# tweeq-Proto_Motor.net
KiCad netlist of a schematic drawn in EAGLE
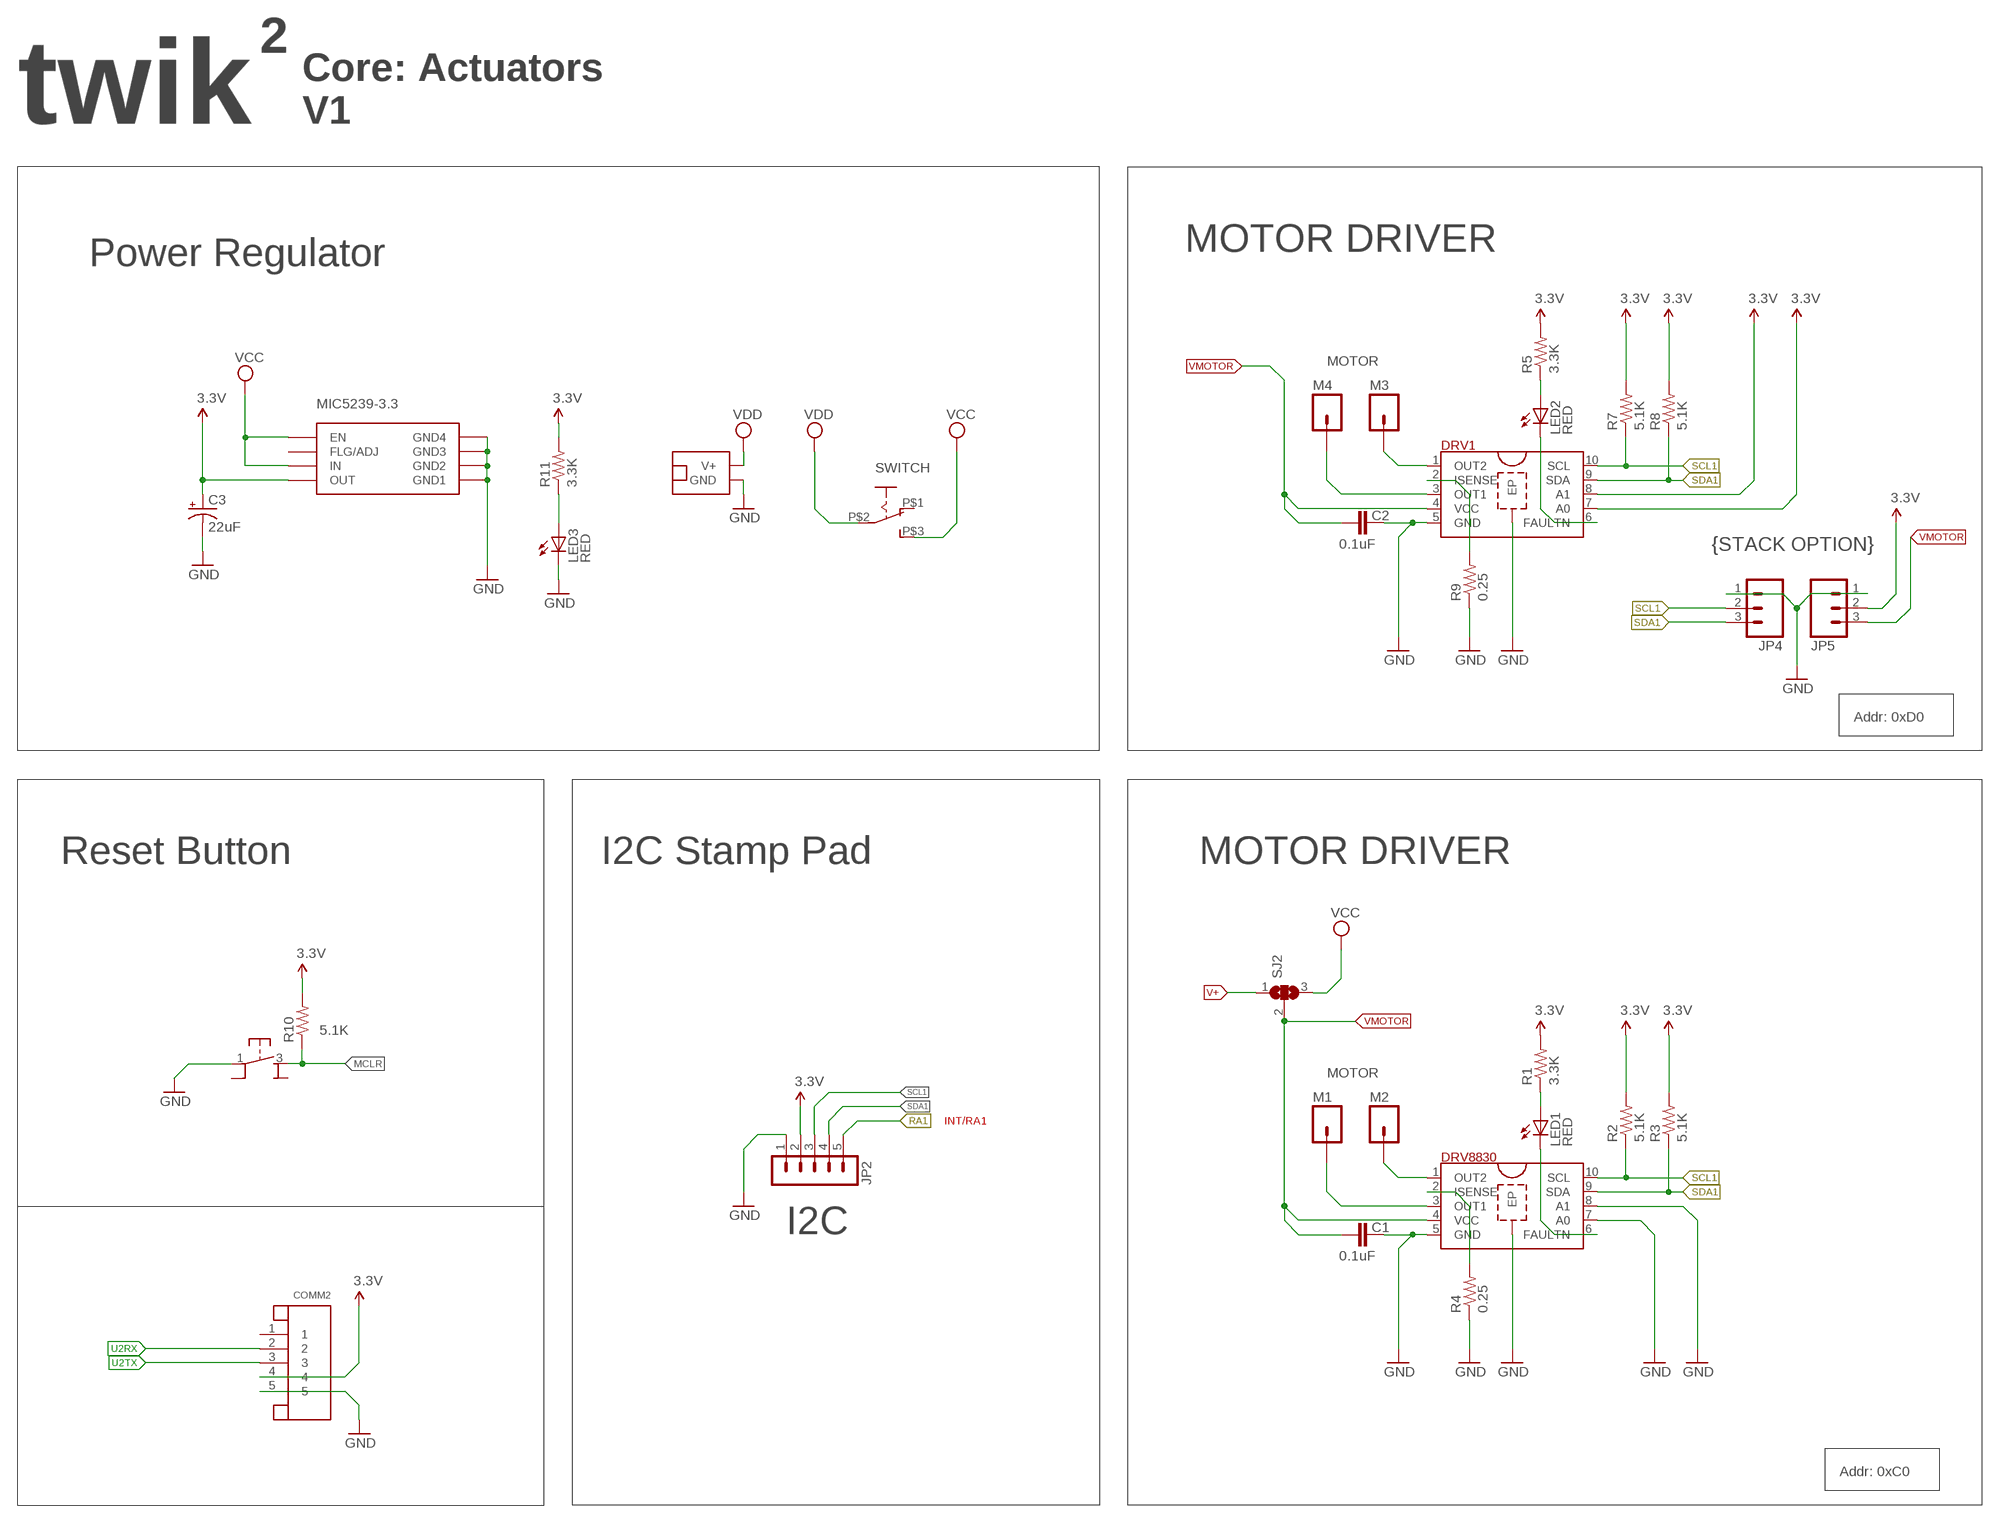
[diagram p0: schematic, sheet 1, part 1 of 2]
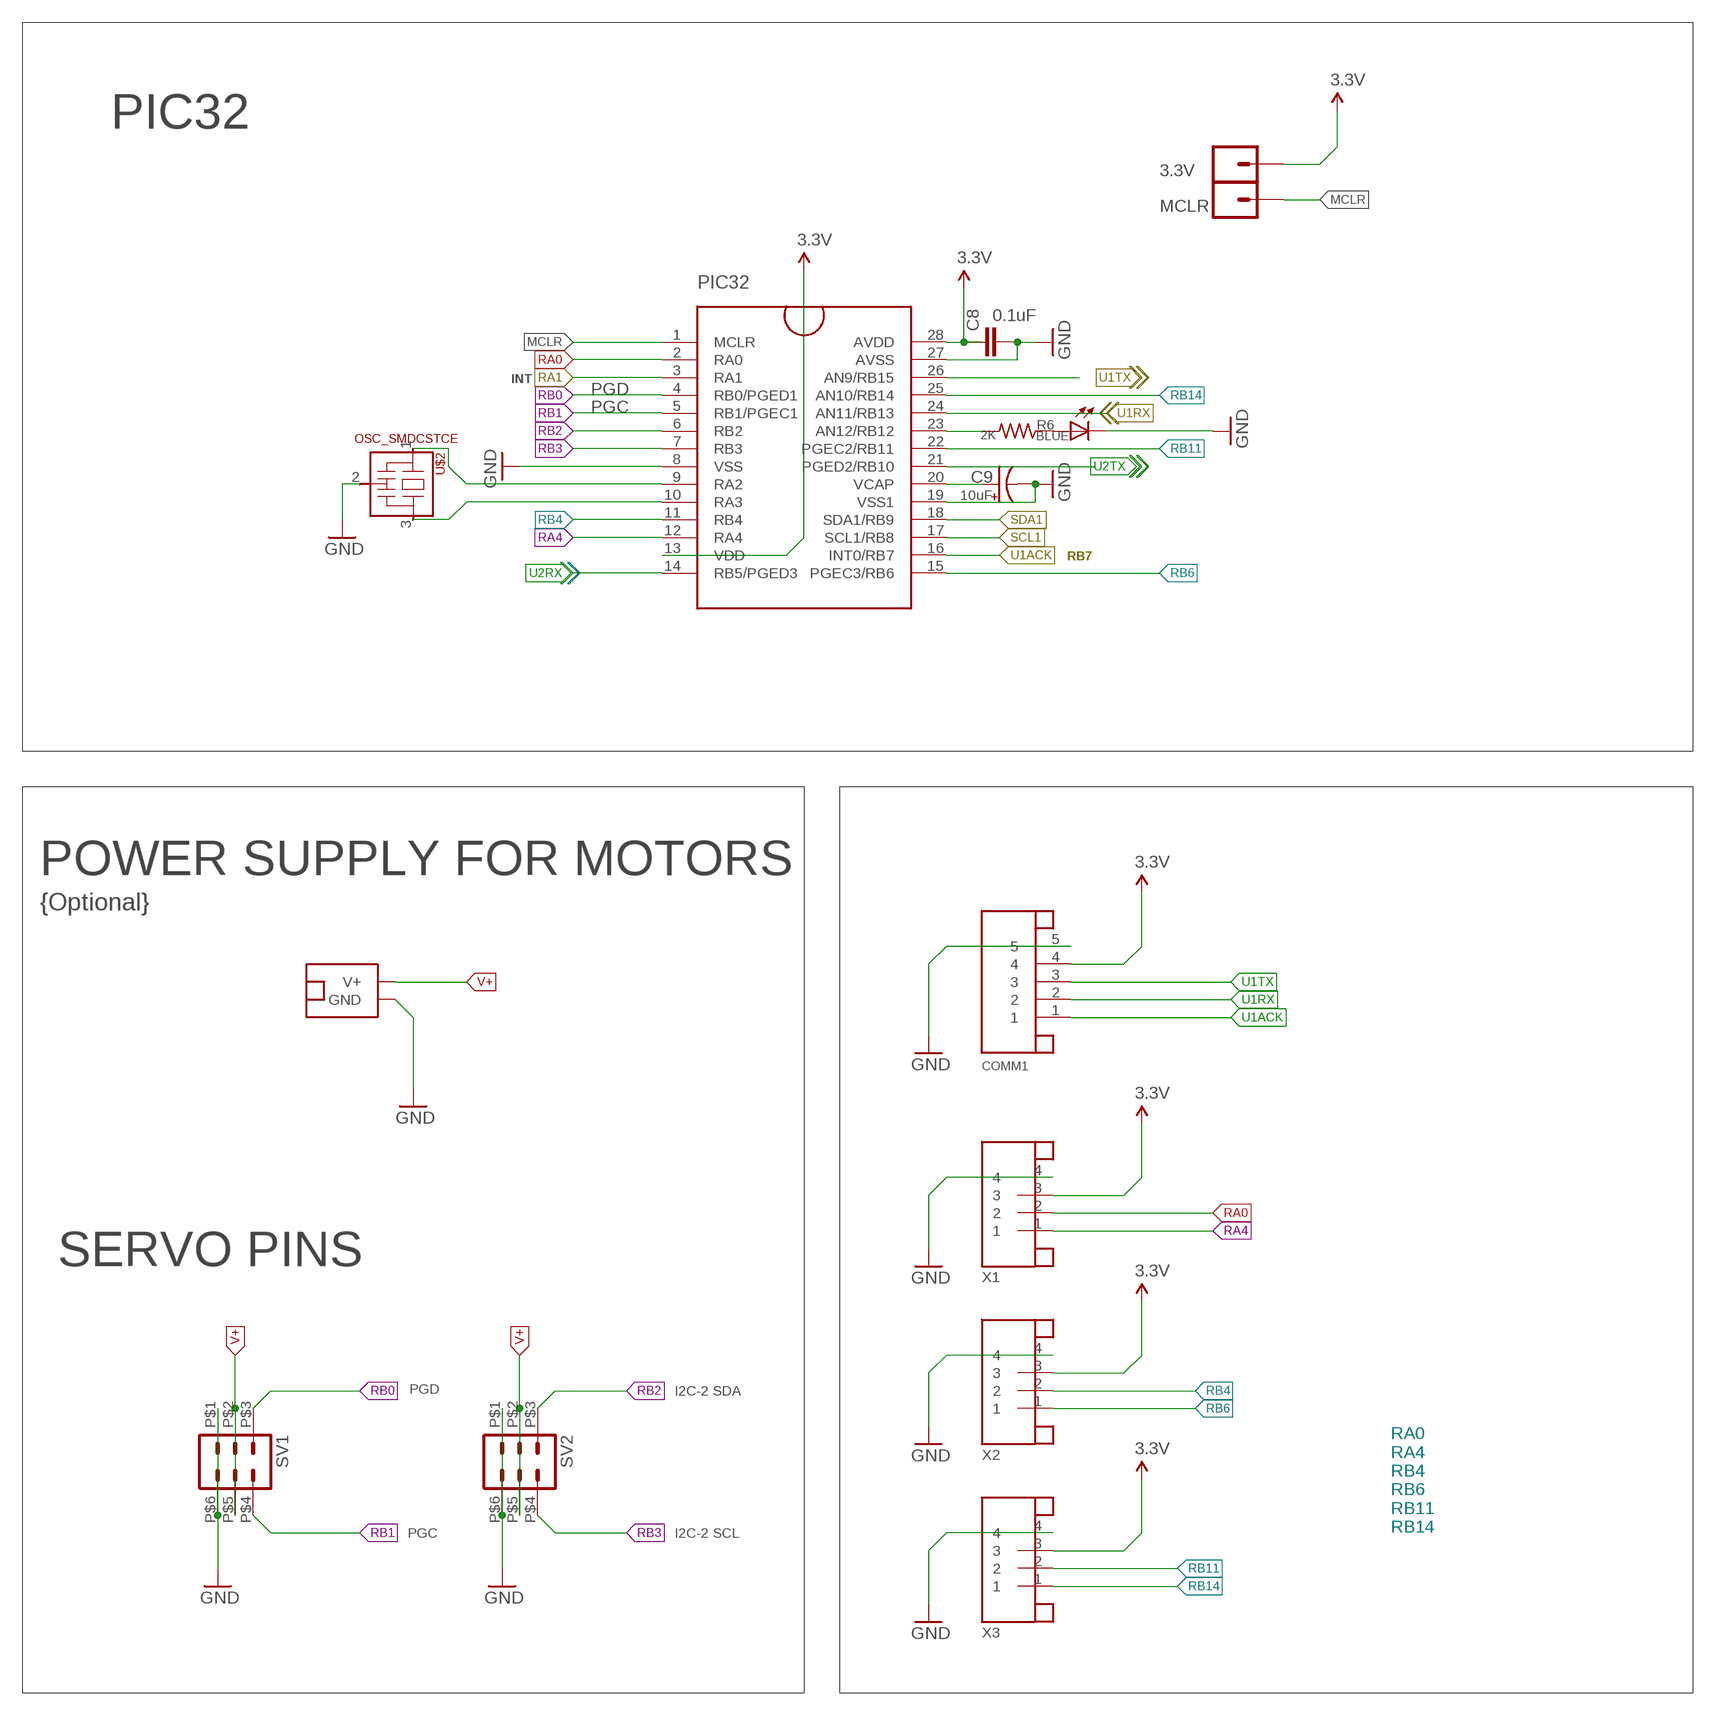
[diagram p1: schematic, sheet 1, part 2 of 2]

(export (version "E")
  (design (tool "Eeschema 10.0.6"))
  (components
    (comp (ref "3.3V")
      (value "M01")
      (footprint "eagle-import:AISCUBE_1X01_TIGHTFITVIA")
      (libsource (lib "eagle-import") (part "M01"))
    )
    (comp (ref "C1")
      (value "0.1uF")
      (footprint "eagle-import:C0402K")
      (libsource (lib "eagle-import") (part "C-EUC0402K"))
    )
    (comp (ref "C2")
      (value "0.1uF")
      (footprint "eagle-import:C0402K")
      (libsource (lib "eagle-import") (part "C-EUC0402K"))
    )
    (comp (ref "C3")
      (value "22uF")
      (footprint "eagle-import:SMC_B")
      (libsource (lib "eagle-import") (part "CPOL-USSMCB"))
    )
    (comp (ref "C8")
      (value "0.1uF")
      (footprint "eagle-import:C0402K")
      (libsource (lib "eagle-import") (part "rcl_C-EUC0402K"))
    )
    (comp (ref "C9")
      (value "10uF")
      (footprint "eagle-import:A_3216-18R")
      (libsource (lib "eagle-import") (part "CPOL-USA/3216-18R"))
    )
    (comp (ref "COMM1")
      (value "JST-5PINSH")
      (footprint "eagle-import:SH1.0-5PIN")
      (libsource (lib "eagle-import") (part "JST-5PINSH"))
    )
    (comp (ref "COMM2")
      (value "JST-5PINSH")
      (footprint "eagle-import:SH1.0-5PIN")
      (libsource (lib "eagle-import") (part "JST-5PINSH"))
    )
    (comp (ref "DRV1")
      (value "DRV8830DGQ")
      (footprint "eagle-import:MSOP10_POWERPAD")
      (libsource (lib "eagle-import") (part "DRV8830DGQ"))
    )
    (comp (ref "DRV8830")
      (value "DRV8830DGQ")
      (footprint "eagle-import:MSOP10_POWERPAD")
      (libsource (lib "eagle-import") (part "DRV8830DGQ"))
    )
    (comp (ref "JP2")
      (value "M05-11.5MM-SMT")
      (footprint "eagle-import:1X05-1.5MM-SMT")
      (libsource (lib "eagle-import") (part "M05-11.5MM-SMT"))
    )
    (comp (ref "JP4")
      (value "M03/NS")
      (footprint "eagle-import:1X03_NS")
      (libsource (lib "eagle-import") (part "M03/NS"))
    )
    (comp (ref "JP5")
      (value "M03/NS")
      (footprint "eagle-import:1X03_NS")
      (libsource (lib "eagle-import") (part "M03/NS"))
    )
    (comp (ref "LED1")
      (value "RED")
      (footprint "eagle-import:CHIPLED_0805")
      (libsource (lib "eagle-import") (part "LEDCHIPLED_0805"))
    )
    (comp (ref "LED2")
      (value "RED")
      (footprint "eagle-import:CHIPLED_0805")
      (libsource (lib "eagle-import") (part "LEDCHIPLED_0805"))
    )
    (comp (ref "LED3")
      (value "RED")
      (footprint "eagle-import:CHIP-LED0805")
      (libsource (lib "eagle-import") (part "LEDCHIP-LED0805"))
    )
    (comp (ref "M1")
      (value "M01SQ_NS")
      (footprint "eagle-import:1X01_SQ")
      (libsource (lib "eagle-import") (part "M01SQ_NS"))
    )
    (comp (ref "M2")
      (value "M01SQ_NS")
      (footprint "eagle-import:1X01_SQ")
      (libsource (lib "eagle-import") (part "M01SQ_NS"))
    )
    (comp (ref "M3")
      (value "M01SQ_NS")
      (footprint "eagle-import:1X01_SQ")
      (libsource (lib "eagle-import") (part "M01SQ_NS"))
    )
    (comp (ref "M4")
      (value "M01SQ_NS")
      (footprint "eagle-import:1X01_SQ")
      (libsource (lib "eagle-import") (part "M01SQ_NS"))
    )
    (comp (ref "MCLR")
      (value "M01")
      (footprint "eagle-import:AISCUBE_1X01_TIGHTFITVIA")
      (libsource (lib "eagle-import") (part "M01"))
    )
    (comp (ref "MIC5239-3.3")
      (value "MIC5239-MM")
      (footprint "eagle-import:MSOP8")
      (libsource (lib "eagle-import") (part "MIC5239-MM"))
    )
    (comp (ref "PIC32")
      (value "PIC32MX_1XX_2XX")
      (footprint "eagle-import:SSOP28")
      (libsource (lib "eagle-import") (part "PIC32MX_1XX_2XX"))
    )
    (comp (ref "PIC_LED")
      (value "BLUE")
      (footprint "eagle-import:CHIP-LED0805")
      (libsource (lib "eagle-import") (part "LEDCHIP-LED0805"))
    )
    (comp (ref "R1")
      (value "3.3K")
      (footprint "eagle-import:R0402")
      (libsource (lib "eagle-import") (part "R-US_R0402"))
    )
    (comp (ref "R2")
      (value "5.1K")
      (footprint "eagle-import:R0402")
      (libsource (lib "eagle-import") (part "R-US_R0402"))
    )
    (comp (ref "R3")
      (value "5.1K")
      (footprint "eagle-import:R0402")
      (libsource (lib "eagle-import") (part "R-US_R0402"))
    )
    (comp (ref "R4")
      (value "0.25")
      (footprint "eagle-import:R0402")
      (libsource (lib "eagle-import") (part "R-US_R0402"))
    )
    (comp (ref "R5")
      (value "3.3K")
      (footprint "eagle-import:R0402")
      (libsource (lib "eagle-import") (part "R-US_R0402"))
    )
    (comp (ref "R6")
      (value "2K")
      (footprint "eagle-import:R0402")
      (libsource (lib "eagle-import") (part "R-US_R0402"))
    )
    (comp (ref "R7")
      (value "5.1K")
      (footprint "eagle-import:R0402")
      (libsource (lib "eagle-import") (part "R-US_R0402"))
    )
    (comp (ref "R8")
      (value "5.1K")
      (footprint "eagle-import:R0402")
      (libsource (lib "eagle-import") (part "R-US_R0402"))
    )
    (comp (ref "R9")
      (value "0.25")
      (footprint "eagle-import:R0402")
      (libsource (lib "eagle-import") (part "R-US_R0402"))
    )
    (comp (ref "R10")
      (value "5.1K")
      (footprint "eagle-import:R0402")
      (libsource (lib "eagle-import") (part "R-US_R0402"))
    )
    (comp (ref "R11")
      (value "3.3K")
      (footprint "eagle-import:R0402")
      (libsource (lib "eagle-import") (part "R-US_R0402"))
    )
    (comp (ref "SJ2")
      (value "JUMPER_SJ2W")
      (footprint "eagle-import:JUMPER_SJ_2")
      (libsource (lib "eagle-import") (part "JUMPER_SJ2W"))
    )
    (comp (ref "SV1")
      (value "M03-2EDGE_PAD")
      (footprint "eagle-import:2X03_EDGEPAD")
      (libsource (lib "eagle-import") (part "M03-2EDGE_PAD"))
    )
    (comp (ref "SV2")
      (value "M03-2EDGE_PAD")
      (footprint "eagle-import:2X03_EDGEPAD")
      (libsource (lib "eagle-import") (part "M03-2EDGE_PAD"))
    )
    (comp (ref "SWITCH")
      (value "SLIDE_SWITCH_SMALL")
      (footprint "eagle-import:SLIDE_SWITCH_SMALL")
      (libsource (lib "eagle-import") (part "SLIDE_SWITCH_SMALL"))
    )
    (comp (ref "U$2")
      (value "OSC_SMDCSTCE")
      (footprint "eagle-import:CSTCE_RESONATOR_SMD")
      (libsource (lib "eagle-import") (part "OSC_SMDCSTCE"))
    )
    (comp (ref "U$4")
      (value "PB_MICRO_SMT")
      (footprint "eagle-import:PB_SMT_3.5X3X2")
      (libsource (lib "eagle-import") (part "PB_MICRO_SMT"))
    )
    (comp (ref "U$9")
      (value "POWER_CONN/PTH")
      (footprint "eagle-import:POWER_CONN_PTH")
      (libsource (lib "eagle-import") (part "POWER_CONN/PTH"))
    )
    (comp (ref "U$10")
      (value "POWER_CONN/PTH")
      (footprint "eagle-import:POWER_CONN_PTH")
      (libsource (lib "eagle-import") (part "POWER_CONN/PTH"))
    )
    (comp (ref "X1")
      (value "JST-4PINSH")
      (footprint "eagle-import:SH1.0-4PIN")
      (libsource (lib "eagle-import") (part "JST-4PINSH"))
    )
    (comp (ref "X2")
      (value "JST-4PINSH")
      (footprint "eagle-import:SH1.0-4PIN")
      (libsource (lib "eagle-import") (part "JST-4PINSH"))
    )
    (comp (ref "X3")
      (value "JST-4PINSH")
      (footprint "eagle-import:SH1.0-4PIN")
      (libsource (lib "eagle-import") (part "JST-4PINSH"))
    )
  )
  (nets
    (net (code "1") (name "3.3V") (class "Default")
      (node (ref "3.3V") (pin "P$1") (pinfunction "1_P$1") (pintype "passive"))
      (node (ref "C3") (pin "+") (pinfunction "+_+") (pintype "passive"))
      (node (ref "C8") (pin "1") (pinfunction "1_1") (pintype "passive"))
      (node (ref "COMM1") (pin "4") (pinfunction "4_4") (pintype "bidirectional"))
      (node (ref "COMM2") (pin "4") (pinfunction "4_4") (pintype "bidirectional"))
      (node (ref "DRV1") (pin "7") (pinfunction "A0_7") (pintype "bidirectional"))
      (node (ref "DRV1") (pin "8") (pinfunction "A1_8") (pintype "bidirectional"))
      (node (ref "JP2") (pin "2") (pinfunction "2_2") (pintype "passive"))
      (node (ref "JP5") (pin "2") (pinfunction "2_2") (pintype "passive"))
      (node (ref "MIC5239-3.3") (pin "4") (pinfunction "OUT_4") (pintype "bidirectional"))
      (node (ref "PIC32") (pin "13") (pinfunction "VDD_13") (pintype "bidirectional"))
      (node (ref "PIC32") (pin "28") (pinfunction "AVDD_28") (pintype "bidirectional"))
      (node (ref "R1") (pin "2") (pinfunction "2_2") (pintype "passive"))
      (node (ref "R10") (pin "2") (pinfunction "2_2") (pintype "passive"))
      (node (ref "R11") (pin "2") (pinfunction "2_2") (pintype "passive"))
      (node (ref "R2") (pin "2") (pinfunction "2_2") (pintype "passive"))
      (node (ref "R3") (pin "2") (pinfunction "2_2") (pintype "passive"))
      (node (ref "R5") (pin "2") (pinfunction "2_2") (pintype "passive"))
      (node (ref "R7") (pin "2") (pinfunction "2_2") (pintype "passive"))
      (node (ref "R8") (pin "2") (pinfunction "2_2") (pintype "passive"))
      (node (ref "X1") (pin "3") (pinfunction "3_3") (pintype "bidirectional"))
      (node (ref "X2") (pin "3") (pinfunction "3_3") (pintype "bidirectional"))
      (node (ref "X3") (pin "3") (pinfunction "3_3") (pintype "bidirectional"))
    )
    (net (code "2") (name "GND") (class "Default")
      (node (ref "C1") (pin "2") (pinfunction "2_2") (pintype "passive"))
      (node (ref "C2") (pin "2") (pinfunction "2_2") (pintype "passive"))
      (node (ref "C3") (pin "-") (pinfunction "-_-") (pintype "passive"))
      (node (ref "C8") (pin "2") (pinfunction "2_2") (pintype "passive"))
      (node (ref "C9") (pin "-") (pinfunction "-_-") (pintype "passive"))
      (node (ref "COMM1") (pin "5") (pinfunction "5_5") (pintype "bidirectional"))
      (node (ref "COMM2") (pin "5") (pinfunction "5_5") (pintype "bidirectional"))
      (node (ref "DRV1") (pin "5") (pinfunction "GND_5") (pintype "bidirectional"))
      (node (ref "DRV1") (pin "EP") (pinfunction "EP_EP") (pintype "bidirectional"))
      (node (ref "DRV8830") (pin "5") (pinfunction "GND_5") (pintype "bidirectional"))
      (node (ref "DRV8830") (pin "7") (pinfunction "A0_7") (pintype "bidirectional"))
      (node (ref "DRV8830") (pin "8") (pinfunction "A1_8") (pintype "bidirectional"))
      (node (ref "DRV8830") (pin "EP") (pinfunction "EP_EP") (pintype "bidirectional"))
      (node (ref "JP2") (pin "1") (pinfunction "1_1") (pintype "passive"))
      (node (ref "JP4") (pin "1") (pinfunction "1_1") (pintype "passive"))
      (node (ref "JP5") (pin "1") (pinfunction "1_1") (pintype "passive"))
      (node (ref "LED3") (pin "C") (pinfunction "C_C") (pintype "passive"))
      (node (ref "MIC5239-3.3") (pin "5") (pinfunction "GND1_5") (pintype "bidirectional"))
      (node (ref "MIC5239-3.3") (pin "6") (pinfunction "GND2_6") (pintype "bidirectional"))
      (node (ref "MIC5239-3.3") (pin "7") (pinfunction "GND3_7") (pintype "bidirectional"))
      (node (ref "MIC5239-3.3") (pin "8") (pinfunction "GND4_8") (pintype "bidirectional"))
      (node (ref "PIC32") (pin "19") (pinfunction "VSS1_19") (pintype "bidirectional"))
      (node (ref "PIC32") (pin "27") (pinfunction "AVSS_27") (pintype "bidirectional"))
      (node (ref "PIC32") (pin "8") (pinfunction "VSS_8") (pintype "bidirectional"))
      (node (ref "PIC_LED") (pin "C") (pinfunction "C_C") (pintype "passive"))
      (node (ref "R4") (pin "1") (pinfunction "1_1") (pintype "passive"))
      (node (ref "R9") (pin "1") (pinfunction "1_1") (pintype "passive"))
      (node (ref "SV1") (pin "P$1") (pinfunction "1_P$1") (pintype "passive"))
      (node (ref "SV1") (pin "P$6") (pinfunction "6_P$6") (pintype "passive"))
      (node (ref "SV2") (pin "P$1") (pinfunction "1_P$1") (pintype "passive"))
      (node (ref "SV2") (pin "P$6") (pinfunction "6_P$6") (pintype "passive"))
      (node (ref "U$10") (pin "GND") (pinfunction "GND_GND") (pintype "power_in"))
      (node (ref "U$2") (pin "2") (pinfunction "VSS_2") (pintype "power_in"))
      (node (ref "U$4") (pin "1") (pinfunction "1_1") (pintype "passive"))
      (node (ref "U$9") (pin "GND") (pinfunction "GND_GND") (pintype "power_in"))
      (node (ref "X1") (pin "4") (pinfunction "4_4") (pintype "bidirectional"))
      (node (ref "X2") (pin "4") (pinfunction "4_4") (pintype "bidirectional"))
      (node (ref "X3") (pin "4") (pinfunction "4_4") (pintype "bidirectional"))
    )
    (net (code "3") (name "MCLR") (class "Default")
      (node (ref "MCLR") (pin "P$1") (pinfunction "1_P$1") (pintype "passive"))
      (node (ref "PIC32") (pin "1") (pinfunction "MCLR_1") (pintype "bidirectional"))
      (node (ref "R10") (pin "1") (pinfunction "1_1") (pintype "passive"))
      (node (ref "U$4") (pin "3") (pinfunction "2_3") (pintype "passive"))
    )
    (net (code "4") (name "Net-(DRV1-FAULTN)") (class "Default")
      (node (ref "DRV1") (pin "6") (pinfunction "FAULTN_6") (pintype "bidirectional"))
      (node (ref "LED2") (pin "C") (pinfunction "C_C") (pintype "passive"))
    )
    (net (code "5") (name "Net-(DRV1-ISENSE)") (class "Default")
      (node (ref "DRV1") (pin "2") (pinfunction "ISENSE_2") (pintype "bidirectional"))
      (node (ref "R9") (pin "2") (pinfunction "2_2") (pintype "passive"))
    )
    (net (code "6") (name "Net-(DRV1-OUT1)") (class "Default")
      (node (ref "DRV1") (pin "3") (pinfunction "OUT1_3") (pintype "bidirectional"))
      (node (ref "M4") (pin "1") (pinfunction "1_1") (pintype "passive"))
    )
    (net (code "7") (name "Net-(DRV1-OUT2)") (class "Default")
      (node (ref "DRV1") (pin "1") (pinfunction "OUT2_1") (pintype "bidirectional"))
      (node (ref "M3") (pin "1") (pinfunction "1_1") (pintype "passive"))
    )
    (net (code "8") (name "Net-(DRV8830-FAULTN)") (class "Default")
      (node (ref "DRV8830") (pin "6") (pinfunction "FAULTN_6") (pintype "bidirectional"))
      (node (ref "LED1") (pin "C") (pinfunction "C_C") (pintype "passive"))
    )
    (net (code "9") (name "Net-(DRV8830-ISENSE)") (class "Default")
      (node (ref "DRV8830") (pin "2") (pinfunction "ISENSE_2") (pintype "bidirectional"))
      (node (ref "R4") (pin "2") (pinfunction "2_2") (pintype "passive"))
    )
    (net (code "10") (name "Net-(DRV8830-OUT1)") (class "Default")
      (node (ref "DRV8830") (pin "3") (pinfunction "OUT1_3") (pintype "bidirectional"))
      (node (ref "M1") (pin "1") (pinfunction "1_1") (pintype "passive"))
    )
    (net (code "11") (name "Net-(DRV8830-OUT2)") (class "Default")
      (node (ref "DRV8830") (pin "1") (pinfunction "OUT2_1") (pintype "bidirectional"))
      (node (ref "M2") (pin "1") (pinfunction "1_1") (pintype "passive"))
    )
    (net (code "12") (name "Net-(LED1-PadA)") (class "Default")
      (node (ref "LED1") (pin "A") (pinfunction "A_A") (pintype "passive"))
      (node (ref "R1") (pin "1") (pinfunction "1_1") (pintype "passive"))
    )
    (net (code "13") (name "Net-(LED2-PadA)") (class "Default")
      (node (ref "LED2") (pin "A") (pinfunction "A_A") (pintype "passive"))
      (node (ref "R5") (pin "1") (pinfunction "1_1") (pintype "passive"))
    )
    (net (code "14") (name "Net-(LED3-PadA)") (class "Default")
      (node (ref "LED3") (pin "A") (pinfunction "A_A") (pintype "passive"))
      (node (ref "R11") (pin "1") (pinfunction "1_1") (pintype "passive"))
    )
    (net (code "15") (name "Net-(PIC32-AN12{slash}RB12)") (class "Default")
      (node (ref "PIC32") (pin "23") (pinfunction "AN12/RB12_23") (pintype "bidirectional"))
      (node (ref "R6") (pin "2") (pinfunction "2_2") (pintype "passive"))
    )
    (net (code "16") (name "Net-(PIC32-RA2)") (class "Default")
      (node (ref "PIC32") (pin "9") (pinfunction "RA2_9") (pintype "bidirectional"))
      (node (ref "U$2") (pin "1") (pinfunction "1_1") (pintype "output"))
    )
    (net (code "17") (name "Net-(PIC32-RA3)") (class "Default")
      (node (ref "PIC32") (pin "10") (pinfunction "RA3_10") (pintype "bidirectional"))
      (node (ref "U$2") (pin "3") (pinfunction "3_3") (pintype "input"))
    )
    (net (code "18") (name "Net-(PIC32-VCAP)") (class "Default")
      (node (ref "C9") (pin "+") (pinfunction "+_+") (pintype "passive"))
      (node (ref "PIC32") (pin "20") (pinfunction "VCAP_20") (pintype "bidirectional"))
    )
    (net (code "19") (name "Net-(PIC_LED-PadA)") (class "Default")
      (node (ref "PIC_LED") (pin "A") (pinfunction "A_A") (pintype "passive"))
      (node (ref "R6") (pin "1") (pinfunction "1_1") (pintype "passive"))
    )
    (net (code "20") (name "RA0") (class "Default")
      (node (ref "PIC32") (pin "2") (pinfunction "RA0_2") (pintype "bidirectional"))
      (node (ref "X1") (pin "2") (pinfunction "2_2") (pintype "bidirectional"))
    )
    (net (code "21") (name "RA1") (class "Default")
      (node (ref "JP2") (pin "5") (pinfunction "5_5") (pintype "passive"))
      (node (ref "PIC32") (pin "3") (pinfunction "RA1_3") (pintype "bidirectional"))
    )
    (net (code "22") (name "RA4") (class "Default")
      (node (ref "PIC32") (pin "12") (pinfunction "RA4_12") (pintype "bidirectional"))
      (node (ref "X1") (pin "1") (pinfunction "1_1") (pintype "bidirectional"))
    )
    (net (code "23") (name "RB0") (class "Default")
      (node (ref "PIC32") (pin "4") (pinfunction "RB0/PGED1_4") (pintype "bidirectional"))
      (node (ref "SV1") (pin "P$3") (pinfunction "3_P$3") (pintype "passive"))
    )
    (net (code "24") (name "RB1") (class "Default")
      (node (ref "PIC32") (pin "5") (pinfunction "RB1/PGEC1_5") (pintype "bidirectional"))
      (node (ref "SV1") (pin "P$4") (pinfunction "4_P$4") (pintype "passive"))
    )
    (net (code "25") (name "RB2") (class "Default")
      (node (ref "PIC32") (pin "6") (pinfunction "RB2_6") (pintype "bidirectional"))
      (node (ref "SV2") (pin "P$3") (pinfunction "3_P$3") (pintype "passive"))
    )
    (net (code "26") (name "RB3") (class "Default")
      (node (ref "PIC32") (pin "7") (pinfunction "RB3_7") (pintype "bidirectional"))
      (node (ref "SV2") (pin "P$4") (pinfunction "4_P$4") (pintype "passive"))
    )
    (net (code "27") (name "RB4") (class "Default")
      (node (ref "PIC32") (pin "11") (pinfunction "RB4_11") (pintype "bidirectional"))
      (node (ref "X2") (pin "2") (pinfunction "2_2") (pintype "bidirectional"))
    )
    (net (code "28") (name "RB6") (class "Default")
      (node (ref "PIC32") (pin "15") (pinfunction "PGEC3/RB6_15") (pintype "bidirectional"))
      (node (ref "X2") (pin "1") (pinfunction "1_1") (pintype "bidirectional"))
    )
    (net (code "29") (name "RB11") (class "Default")
      (node (ref "PIC32") (pin "22") (pinfunction "PGEC2/RB11_22") (pintype "bidirectional"))
      (node (ref "X3") (pin "2") (pinfunction "2_2") (pintype "bidirectional"))
    )
    (net (code "30") (name "RB14") (class "Default")
      (node (ref "PIC32") (pin "25") (pinfunction "AN10/RB14_25") (pintype "bidirectional"))
      (node (ref "X3") (pin "1") (pinfunction "1_1") (pintype "bidirectional"))
    )
    (net (code "31") (name "SCL1") (class "Default")
      (node (ref "DRV1") (pin "10") (pinfunction "SCL_10") (pintype "bidirectional"))
      (node (ref "DRV8830") (pin "10") (pinfunction "SCL_10") (pintype "bidirectional"))
      (node (ref "JP2") (pin "3") (pinfunction "3_3") (pintype "passive"))
      (node (ref "JP4") (pin "2") (pinfunction "2_2") (pintype "passive"))
      (node (ref "PIC32") (pin "17") (pinfunction "SCL1/RB8_17") (pintype "bidirectional"))
      (node (ref "R2") (pin "1") (pinfunction "1_1") (pintype "passive"))
      (node (ref "R7") (pin "1") (pinfunction "1_1") (pintype "passive"))
    )
    (net (code "32") (name "SDA1") (class "Default")
      (node (ref "DRV1") (pin "9") (pinfunction "SDA_9") (pintype "bidirectional"))
      (node (ref "DRV8830") (pin "9") (pinfunction "SDA_9") (pintype "bidirectional"))
      (node (ref "JP2") (pin "4") (pinfunction "4_4") (pintype "passive"))
      (node (ref "JP4") (pin "3") (pinfunction "3_3") (pintype "passive"))
      (node (ref "PIC32") (pin "18") (pinfunction "SDA1/RB9_18") (pintype "bidirectional"))
      (node (ref "R3") (pin "1") (pinfunction "1_1") (pintype "passive"))
      (node (ref "R8") (pin "1") (pinfunction "1_1") (pintype "passive"))
    )
    (net (code "33") (name "U1ACK") (class "Default")
      (node (ref "COMM1") (pin "1") (pinfunction "1_1") (pintype "bidirectional"))
      (node (ref "PIC32") (pin "16") (pinfunction "INT0/RB7_16") (pintype "bidirectional"))
    )
    (net (code "34") (name "U1RX") (class "Default")
      (node (ref "COMM1") (pin "2") (pinfunction "2_2") (pintype "bidirectional"))
      (node (ref "PIC32") (pin "24") (pinfunction "AN11/RB13_24") (pintype "bidirectional"))
    )
    (net (code "35") (name "U1TX") (class "Default")
      (node (ref "COMM1") (pin "3") (pinfunction "3_3") (pintype "bidirectional"))
      (node (ref "PIC32") (pin "26") (pinfunction "AN9/RB15_26") (pintype "bidirectional"))
    )
    (net (code "36") (name "U2RX") (class "Default")
      (node (ref "COMM2") (pin "2") (pinfunction "2_2") (pintype "bidirectional"))
      (node (ref "PIC32") (pin "14") (pinfunction "RB5/PGED3_14") (pintype "bidirectional"))
    )
    (net (code "37") (name "U2TX") (class "Default")
      (node (ref "COMM2") (pin "3") (pinfunction "3_3") (pintype "bidirectional"))
      (node (ref "PIC32") (pin "21") (pinfunction "PGED2/RB10_21") (pintype "bidirectional"))
    )
    (net (code "38") (name "V+") (class "Default")
      (node (ref "SJ2") (pin "1") (pinfunction "1_1") (pintype "passive"))
      (node (ref "SV1") (pin "P$2") (pinfunction "2_P$2") (pintype "passive"))
      (node (ref "SV1") (pin "P$5") (pinfunction "5_P$5") (pintype "passive"))
      (node (ref "SV2") (pin "P$2") (pinfunction "2_P$2") (pintype "passive"))
      (node (ref "SV2") (pin "P$5") (pinfunction "5_P$5") (pintype "passive"))
      (node (ref "U$10") (pin "V+") (pinfunction "V+_V+") (pintype "power_in"))
    )
    (net (code "39") (name "VCC") (class "Default")
      (node (ref "MIC5239-3.3") (pin "1") (pinfunction "EN_1") (pintype "bidirectional"))
      (node (ref "MIC5239-3.3") (pin "3") (pinfunction "IN_3") (pintype "bidirectional"))
      (node (ref "SJ2") (pin "3") (pinfunction "3_3") (pintype "passive"))
      (node (ref "SWITCH") (pin "P$3") (pinfunction "S_P$3") (pintype "passive"))
    )
    (net (code "40") (name "VDD") (class "Default")
      (node (ref "SWITCH") (pin "P$2") (pinfunction "P_P$2") (pintype "passive"))
      (node (ref "U$9") (pin "V+") (pinfunction "V+_V+") (pintype "power_in"))
    )
    (net (code "41") (name "VMOTOR") (class "Default")
      (node (ref "C1") (pin "1") (pinfunction "1_1") (pintype "passive"))
      (node (ref "C2") (pin "1") (pinfunction "1_1") (pintype "passive"))
      (node (ref "DRV1") (pin "4") (pinfunction "VCC_4") (pintype "bidirectional"))
      (node (ref "DRV8830") (pin "4") (pinfunction "VCC_4") (pintype "bidirectional"))
      (node (ref "JP5") (pin "3") (pinfunction "3_3") (pintype "passive"))
      (node (ref "SJ2") (pin "2") (pinfunction "2_2") (pintype "passive"))
    )
    (net (code "42") (name "unconnected-(COMM2-Pad1)") (class "Default")
      (node (ref "COMM2") (pin "1") (pinfunction "1_1") (pintype "bidirectional"))
    )
    (net (code "43") (name "unconnected-(MIC5239-3.3-FLG{slash}ADJ-Pad2)") (class "Default")
      (node (ref "MIC5239-3.3") (pin "2") (pinfunction "FLG/ADJ_2") (pintype "bidirectional"))
    )
    (net (code "44") (name "unconnected-(SWITCH-O-PadP$1)") (class "Default")
      (node (ref "SWITCH") (pin "P$1") (pinfunction "O_P$1") (pintype "passive"))
    )
    (net (code "45") (name "unconnected-(U$4-1A-Pad2)") (class "Default")
      (node (ref "U$4") (pin "2") (pinfunction "1A_2") (pintype "passive"))
    )
    (net (code "46") (name "unconnected-(U$4-2A-Pad4)") (class "Default")
      (node (ref "U$4") (pin "4") (pinfunction "2A_4") (pintype "passive"))
    )
  )
)
